# interface.net
KiCad netlist of a schematic drawn in Altium Designer
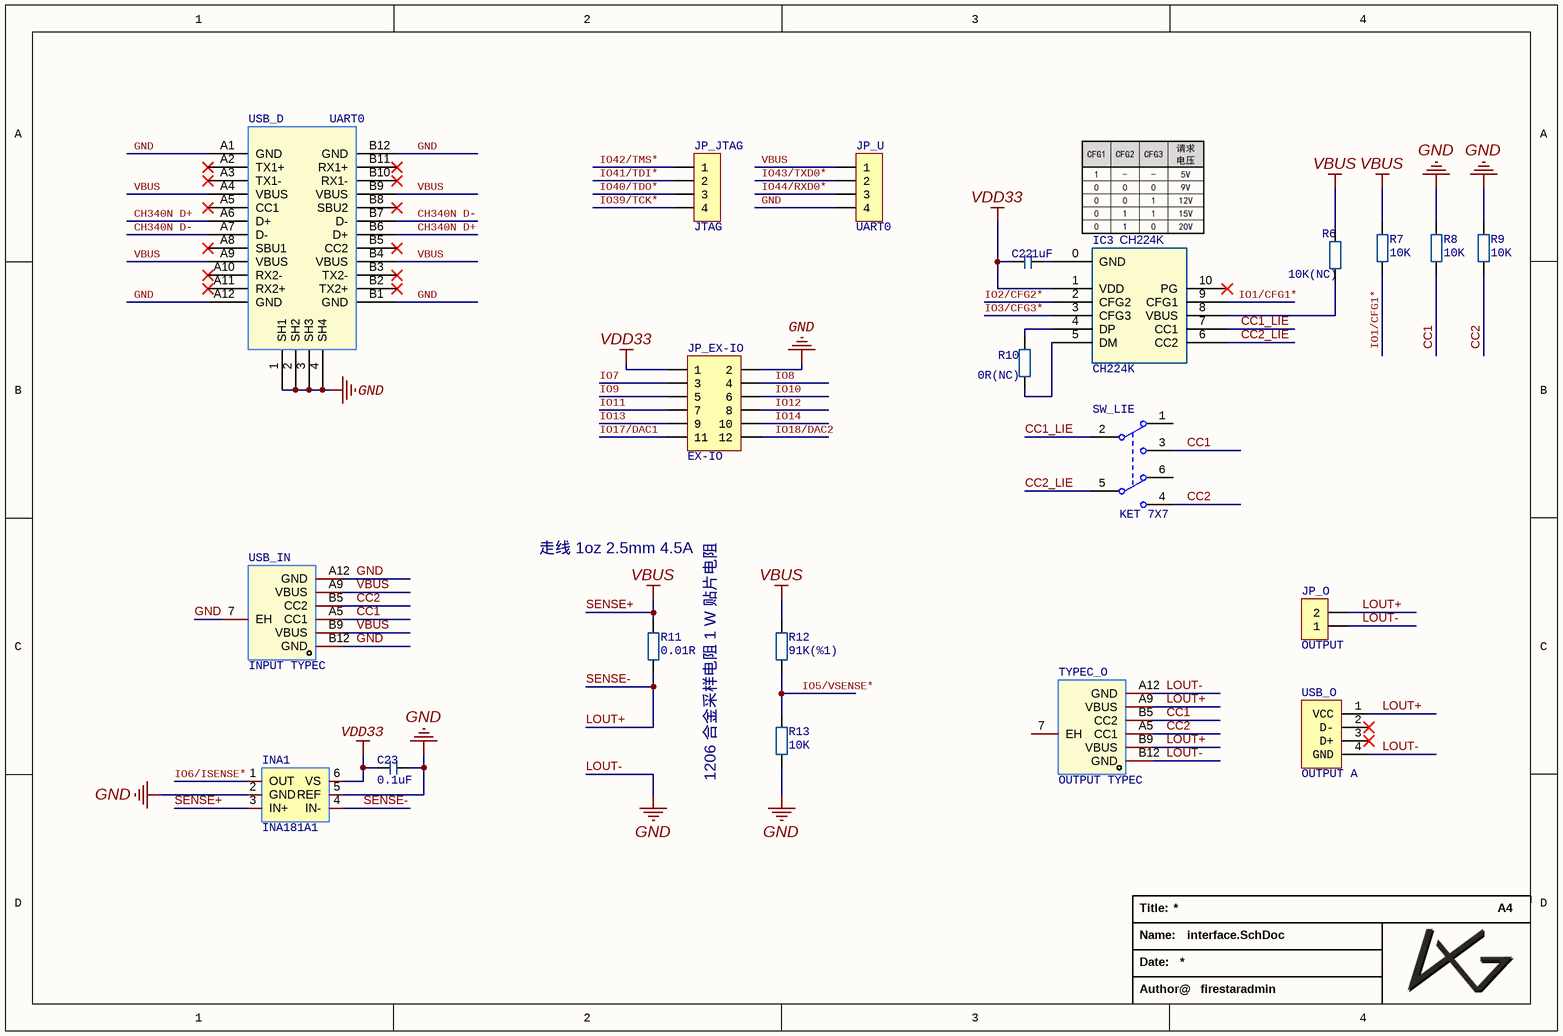
[diagram p0: interface.SchDoc]

(export (version "E")
  (design (tool "Eeschema 10.0.6"))
  (components
    (comp (ref "C22")
      (value "1uF")
      (footprint "C 0603_L")
      (description "无极性贴片电容")
      (fields (field (name "版权归属") "源创客"))
      (libsource (lib "SCH-电阻-电容-电感") (part "C"))
    )
    (comp (ref "C23")
      (value "0.1uF")
      (footprint "C 0603_L")
      (description "无极性贴片电容")
      (fields (field (name "版权归属") "源创客"))
      (libsource (lib "SCH-电阻-电容-电感") (part "C"))
    )
    (comp (ref "IC3")
      (value "CH224K")
      (footprint "ESSOP10-1mm")
      (libsource (lib "SCH-电源类芯片") (part "CH224K"))
    )
    (comp (ref "INA1")
      (value "INA181A1")
      (footprint "SOT23-6L")
      (description "电流检测")
      (libsource (lib "SCH-IC芯片") (part "INA181A1"))
    )
    (comp (ref "JP_EX-IO")
      (value "EX-IO")
      (footprint "HDR2.54-LI-2x6P")
      (description "6*2P接插件")
      (fields (field (name "版权归属") "源创客"))
      (libsource (lib "SCH-接插件-2.54mm") (part "Header  6X2"))
    )
    (comp (ref "JP_JTAG")
      (value "JTAG")
      (footprint "HDR2.54-LI-4P")
      (description "4P接插件")
      (fields (field (name "版权归属") "源创客"))
      (libsource (lib "SCH-接插件-2.54mm") (part "Header 4"))
    )
    (comp (ref "JP_O")
      (value "OUTPUT")
      (footprint "KF301-5.0-2P")
      (description "2P接插件")
      (fields (field (name "版权归属") "源创客"))
      (libsource (lib "SCH-接插件-5.0mm") (part "Header 2"))
    )
    (comp (ref "JP_U")
      (value "UART0")
      (footprint "HDR2.54-LI-4P")
      (description "4P接插件")
      (fields (field (name "版权归属") "源创客"))
      (libsource (lib "SCH-接插件-2.54mm") (part "Header 4"))
    )
    (comp (ref "R6")
      (value "10K(NC)")
      (footprint "R 0603_L")
      (description "贴片电阻")
      (fields (field (name "版权归属") "源创客"))
      (libsource (lib "SCH-电阻-电容-电感") (part "R"))
    )
    (comp (ref "R7")
      (value "10K")
      (footprint "R 0603_L")
      (description "贴片电阻")
      (fields (field (name "版权归属") "源创客"))
      (libsource (lib "SCH-电阻-电容-电感") (part "R"))
    )
    (comp (ref "R8")
      (value "10K")
      (footprint "R 0603_L")
      (description "贴片电阻")
      (fields (field (name "版权归属") "源创客"))
      (libsource (lib "SCH-电阻-电容-电感") (part "R"))
    )
    (comp (ref "R9")
      (value "10K")
      (footprint "R 0603_L")
      (description "贴片电阻")
      (fields (field (name "版权归属") "源创客"))
      (libsource (lib "SCH-电阻-电容-电感") (part "R"))
    )
    (comp (ref "R10")
      (value "0R(NC)")
      (footprint "R 0603_L")
      (description "贴片电阻")
      (fields (field (name "版权归属") "源创客"))
      (libsource (lib "SCH-电阻-电容-电感") (part "R"))
    )
    (comp (ref "R11")
      (value "0.01R")
      (footprint "R 1206_L")
      (description "1206 合金采样电阻 1 W 贴片电阻")
      (fields (field (name "版权归属") "源创客"))
      (libsource (lib "SCH-电阻-电容-电感") (part "R"))
    )
    (comp (ref "R12")
      (value "91K(%1)")
      (footprint "R 0603_L")
      (description "贴片电阻")
      (fields (field (name "版权归属") "源创客"))
      (libsource (lib "SCH-电阻-电容-电感") (part "R"))
    )
    (comp (ref "R13")
      (value "10K")
      (footprint "R 0603_L")
      (description "贴片电阻")
      (fields (field (name "版权归属") "源创客"))
      (libsource (lib "SCH-电阻-电容-电感") (part "R"))
    )
    (comp (ref "SW_LIE")
      (value "KET 7X7")
      (footprint "KFT DIP-7X7")
      (description "7*7自锁开关")
      (fields (field (name "版权归属") "源创客"))
      (libsource (lib "SCH-按键-开关") (part "KET 7X7"))
    )
    (comp (ref "TYPEC_O")
      (value "OUTPUT TYPEC")
      (footprint "TYPE-C-6P")
      (fields (field (name "MANUFACTURER") "SHOU HAN(首韩)") (field (name "MANUFACTURER PART") "TYPE-C 6P"))
      (libsource (lib "SCH-接口类") (part "TYPE-C 6P"))
    )
    (comp (ref "USB_D")
      (value "UART0")
      (footprint "TYPE-C-16P")
      (description "Type-C 16Pin")
      (libsource (lib "SCH-接口类") (part "TypeC-16P"))
    )
    (comp (ref "USB_IN")
      (value "INPUT TYPEC")
      (footprint "TYPE-C-6P")
      (fields (field (name "MANUFACTURER") "SHOU HAN(首韩)") (field (name "MANUFACTURER PART") "TYPE-C 6P"))
      (libsource (lib "SCH-接口类") (part "TYPE-C 6P"))
    )
    (comp (ref "USB_O")
      (value "OUTPUT A")
      (footprint "USB-A/S_B")
      (description "USB-A型母接口")
      (fields (field (name "版权归属") "源创客"))
      (libsource (lib "SCH-接口类") (part "USB-A/S"))
    )
  )
  (nets
    (net (code "1") (name "/CC1") (class "Default")
      (node (ref "R8") (pin "2") (pinfunction "2_2") (pintype "passive"))
      (node (ref "SW_LIE") (pin "3") (pinfunction "NO1_3") (pintype "passive"))
      (node (ref "TYPEC_O") (pin "B5") (pinfunction "CC2_B5") (pintype "passive"))
      (node (ref "USB_IN") (pin "A5") (pinfunction "CC1_A5") (pintype "passive"))
    )
    (net (code "2") (name "/CC1_LIE") (class "Default")
      (node (ref "IC3") (pin "7") (pinfunction "CC1_7") (pintype "passive"))
      (node (ref "SW_LIE") (pin "2") (pinfunction "COM2_2") (pintype "passive"))
    )
    (net (code "3") (name "/CC2") (class "Default")
      (node (ref "R9") (pin "2") (pinfunction "2_2") (pintype "passive"))
      (node (ref "SW_LIE") (pin "4") (pinfunction "NO2_4") (pintype "passive"))
      (node (ref "TYPEC_O") (pin "A5") (pinfunction "CC1_A5") (pintype "passive"))
      (node (ref "USB_IN") (pin "B5") (pinfunction "CC2_B5") (pintype "passive"))
    )
    (net (code "4") (name "/CC2_LIE") (class "Default")
      (node (ref "IC3") (pin "6") (pinfunction "CC2_6") (pintype "passive"))
      (node (ref "SW_LIE") (pin "5") (pinfunction "COM2_5") (pintype "passive"))
    )
    (net (code "5") (name "/CH340N D+") (class "Default")
      (node (ref "USB_D") (pin "A6") (pinfunction "D+_A6") (pintype "passive"))
      (node (ref "USB_D") (pin "B6") (pinfunction "D+_B6") (pintype "passive"))
    )
    (net (code "6") (name "/CH340N D-") (class "Default")
      (node (ref "USB_D") (pin "A7") (pinfunction "D-_A7") (pintype "passive"))
      (node (ref "USB_D") (pin "B7") (pinfunction "D-_B7") (pintype "passive"))
    )
    (net (code "7") (name "/IO1{slash}CFG1*") (class "Default")
      (node (ref "IC3") (pin "9") (pinfunction "CFG1_9") (pintype "passive"))
      (node (ref "R7") (pin "2") (pinfunction "2_2") (pintype "passive"))
    )
    (net (code "8") (name "/IO2{slash}CFG2*") (class "Default")
      (node (ref "IC3") (pin "2") (pinfunction "CFG2_2") (pintype "passive"))
    )
    (net (code "9") (name "/IO3{slash}CFG3*") (class "Default")
      (node (ref "IC3") (pin "3") (pinfunction "CFG3_3") (pintype "passive"))
    )
    (net (code "10") (name "/IO5{slash}VSENSE*") (class "Default")
      (node (ref "R12") (pin "1") (pinfunction "1_1") (pintype "passive"))
      (node (ref "R13") (pin "2") (pinfunction "2_2") (pintype "passive"))
    )
    (net (code "11") (name "/IO6{slash}ISENSE*") (class "Default")
      (node (ref "INA1") (pin "1") (pinfunction "OUT_1") (pintype "passive"))
    )
    (net (code "12") (name "/IO7") (class "Default")
      (node (ref "JP_EX-IO") (pin "3") (pinfunction "3_3") (pintype "passive"))
    )
    (net (code "13") (name "/IO8") (class "Default")
      (node (ref "JP_EX-IO") (pin "4") (pinfunction "4_4") (pintype "passive"))
    )
    (net (code "14") (name "/IO9") (class "Default")
      (node (ref "JP_EX-IO") (pin "5") (pinfunction "5_5") (pintype "passive"))
    )
    (net (code "15") (name "/IO10") (class "Default")
      (node (ref "JP_EX-IO") (pin "6") (pinfunction "6_6") (pintype "passive"))
    )
    (net (code "16") (name "/IO11") (class "Default")
      (node (ref "JP_EX-IO") (pin "7") (pinfunction "7_7") (pintype "passive"))
    )
    (net (code "17") (name "/IO12") (class "Default")
      (node (ref "JP_EX-IO") (pin "8") (pinfunction "8_8") (pintype "passive"))
    )
    (net (code "18") (name "/IO13") (class "Default")
      (node (ref "JP_EX-IO") (pin "9") (pinfunction "9_9") (pintype "passive"))
    )
    (net (code "19") (name "/IO14") (class "Default")
      (node (ref "JP_EX-IO") (pin "10") (pinfunction "10_10") (pintype "passive"))
    )
    (net (code "20") (name "/IO17{slash}DAC1") (class "Default")
      (node (ref "JP_EX-IO") (pin "11") (pinfunction "11_11") (pintype "passive"))
    )
    (net (code "21") (name "/IO18{slash}DAC2") (class "Default")
      (node (ref "JP_EX-IO") (pin "12") (pinfunction "12_12") (pintype "passive"))
    )
    (net (code "22") (name "/IO39{slash}TCK*") (class "Default")
      (node (ref "JP_JTAG") (pin "4") (pinfunction "4_4") (pintype "passive"))
    )
    (net (code "23") (name "/IO40{slash}TDO*") (class "Default")
      (node (ref "JP_JTAG") (pin "3") (pinfunction "3_3") (pintype "passive"))
    )
    (net (code "24") (name "/IO41{slash}TDI*") (class "Default")
      (node (ref "JP_JTAG") (pin "2") (pinfunction "2_2") (pintype "passive"))
    )
    (net (code "25") (name "/IO42{slash}TMS*") (class "Default")
      (node (ref "JP_JTAG") (pin "1") (pinfunction "1_1") (pintype "passive"))
    )
    (net (code "26") (name "/IO43{slash}TXD0*") (class "Default")
      (node (ref "JP_U") (pin "2") (pinfunction "2_2") (pintype "passive"))
    )
    (net (code "27") (name "/IO44{slash}RXD0*") (class "Default")
      (node (ref "JP_U") (pin "3") (pinfunction "3_3") (pintype "passive"))
    )
    (net (code "28") (name "/LOUT+") (class "Default")
      (node (ref "INA1") (pin "4") (pinfunction "IN-_4") (pintype "passive"))
      (node (ref "JP_O") (pin "2") (pinfunction "2_2") (pintype "passive"))
      (node (ref "R11") (pin "1") (pinfunction "1_1") (pintype "passive"))
      (node (ref "TYPEC_O") (pin "A9") (pinfunction "VBUS_A9") (pintype "passive"))
      (node (ref "TYPEC_O") (pin "B9") (pinfunction "VBUS_B9") (pintype "passive"))
      (node (ref "USB_O") (pin "1") (pinfunction "VCC_1") (pintype "passive"))
    )
    (net (code "29") (name "GND") (class "Default")
      (node (ref "C23") (pin "1") (pinfunction "1_1") (pintype "passive"))
      (node (ref "INA1") (pin "2") (pinfunction "GND_2") (pintype "passive"))
      (node (ref "INA1") (pin "5") (pinfunction "REF_5") (pintype "passive"))
      (node (ref "JP_EX-IO") (pin "2") (pinfunction "2_2") (pintype "passive"))
      (node (ref "JP_O") (pin "1") (pinfunction "1_1") (pintype "passive"))
      (node (ref "JP_U") (pin "4") (pinfunction "4_4") (pintype "passive"))
      (node (ref "R13") (pin "1") (pinfunction "1_1") (pintype "passive"))
      (node (ref "R8") (pin "1") (pinfunction "1_1") (pintype "passive"))
      (node (ref "R9") (pin "1") (pinfunction "1_1") (pintype "passive"))
      (node (ref "TYPEC_O") (pin "A12") (pinfunction "GND_A12") (pintype "passive"))
      (node (ref "TYPEC_O") (pin "B12") (pinfunction "GND_B12") (pintype "passive"))
      (node (ref "USB_D") (pin "1") (pinfunction "SH1_1") (pintype "passive"))
      (node (ref "USB_D") (pin "2") (pinfunction "SH2_2") (pintype "passive"))
      (node (ref "USB_D") (pin "3") (pinfunction "SH3_3") (pintype "passive"))
      (node (ref "USB_D") (pin "4") (pinfunction "SH4_4") (pintype "passive"))
      (node (ref "USB_D") (pin "A1") (pinfunction "GND_A1") (pintype "passive"))
      (node (ref "USB_D") (pin "A12") (pinfunction "GND_A12") (pintype "passive"))
      (node (ref "USB_D") (pin "B1") (pinfunction "GND_B1") (pintype "passive"))
      (node (ref "USB_D") (pin "B12") (pinfunction "GND_B12") (pintype "passive"))
      (node (ref "USB_IN") (pin "7") (pinfunction "EH_7") (pintype "passive"))
      (node (ref "USB_IN") (pin "A12") (pinfunction "GND_A12") (pintype "passive"))
      (node (ref "USB_IN") (pin "B12") (pinfunction "GND_B12") (pintype "passive"))
      (node (ref "USB_O") (pin "4") (pinfunction "GND_4") (pintype "passive"))
    )
    (net (code "30") (name "Net-(IC3-DM)") (class "Default")
      (node (ref "IC3") (pin "5") (pinfunction "DM_5") (pintype "passive"))
      (node (ref "R10") (pin "2") (pinfunction "2_2") (pintype "passive"))
    )
    (net (code "31") (name "Net-(IC3-DP)") (class "Default")
      (node (ref "IC3") (pin "4") (pinfunction "DP_4") (pintype "passive"))
      (node (ref "R10") (pin "1") (pinfunction "1_1") (pintype "passive"))
    )
    (net (code "32") (name "Net-(IC3-GND)") (class "Default")
      (node (ref "C22") (pin "1") (pinfunction "1_1") (pintype "passive"))
      (node (ref "IC3") (pin "0") (pinfunction "GND_0") (pintype "passive"))
    )
    (net (code "33") (name "Net-(IC3-VBUS)") (class "Default")
      (node (ref "IC3") (pin "8") (pinfunction "VBUS_8") (pintype "passive"))
      (node (ref "R6") (pin "2") (pinfunction "2_2") (pintype "passive"))
    )
    (net (code "34") (name "VBUS") (class "Default")
      (node (ref "INA1") (pin "3") (pinfunction "IN+_3") (pintype "passive"))
      (node (ref "JP_U") (pin "1") (pinfunction "1_1") (pintype "passive"))
      (node (ref "R11") (pin "2") (pinfunction "2_2") (pintype "passive"))
      (node (ref "R12") (pin "2") (pinfunction "2_2") (pintype "passive"))
      (node (ref "R6") (pin "1") (pinfunction "1_1") (pintype "passive"))
      (node (ref "R7") (pin "1") (pinfunction "1_1") (pintype "passive"))
      (node (ref "USB_D") (pin "A4") (pinfunction "VBUS_A4") (pintype "passive"))
      (node (ref "USB_D") (pin "A9") (pinfunction "VBUS_A9") (pintype "passive"))
      (node (ref "USB_D") (pin "B4") (pinfunction "VBUS_B4") (pintype "passive"))
      (node (ref "USB_D") (pin "B9") (pinfunction "VBUS_B9") (pintype "passive"))
      (node (ref "USB_IN") (pin "A9") (pinfunction "VBUS_A9") (pintype "passive"))
      (node (ref "USB_IN") (pin "B9") (pinfunction "VBUS_B9") (pintype "passive"))
    )
    (net (code "35") (name "VDD33") (class "Default")
      (node (ref "C22") (pin "2") (pinfunction "2_2") (pintype "passive"))
      (node (ref "C23") (pin "2") (pinfunction "2_2") (pintype "passive"))
      (node (ref "IC3") (pin "1") (pinfunction "VDD_1") (pintype "passive"))
      (node (ref "INA1") (pin "6") (pinfunction "VS_6") (pintype "passive"))
      (node (ref "JP_EX-IO") (pin "1") (pinfunction "1_1") (pintype "passive"))
    )
    (net (code "36") (name "unconnected-(IC3-PG-Pad10)") (class "Default")
      (node (ref "IC3") (pin "10") (pinfunction "PG_10") (pintype "passive+no_connect"))
    )
    (net (code "37") (name "unconnected-(SW_LIE-NC1-Pad1)") (class "Default")
      (node (ref "SW_LIE") (pin "1") (pinfunction "NC1_1") (pintype "passive"))
    )
    (net (code "38") (name "unconnected-(SW_LIE-NC2-Pad6)") (class "Default")
      (node (ref "SW_LIE") (pin "6") (pinfunction "NC2_6") (pintype "passive"))
    )
    (net (code "39") (name "unconnected-(TYPEC_O-EH-Pad7)") (class "Default")
      (node (ref "TYPEC_O") (pin "7") (pinfunction "EH_7") (pintype "passive"))
    )
    (net (code "40") (name "unconnected-(USB_D-CC1-PadA5)") (class "Default")
      (node (ref "USB_D") (pin "A5") (pinfunction "CC1_A5") (pintype "passive+no_connect"))
    )
    (net (code "41") (name "unconnected-(USB_D-CC2-PadB5)") (class "Default")
      (node (ref "USB_D") (pin "B5") (pinfunction "CC2_B5") (pintype "passive+no_connect"))
    )
    (net (code "42") (name "unconnected-(USB_D-RX1+-PadB11)") (class "Default")
      (node (ref "USB_D") (pin "B11") (pinfunction "RX1+_B11") (pintype "passive+no_connect"))
    )
    (net (code "43") (name "unconnected-(USB_D-RX1--PadB10)") (class "Default")
      (node (ref "USB_D") (pin "B10") (pinfunction "RX1-_B10") (pintype "passive+no_connect"))
    )
    (net (code "44") (name "unconnected-(USB_D-RX2+-PadA11)") (class "Default")
      (node (ref "USB_D") (pin "A11") (pinfunction "RX2+_A11") (pintype "passive+no_connect"))
    )
    (net (code "45") (name "unconnected-(USB_D-RX2--PadA10)") (class "Default")
      (node (ref "USB_D") (pin "A10") (pinfunction "RX2-_A10") (pintype "passive+no_connect"))
    )
    (net (code "46") (name "unconnected-(USB_D-SBU1-PadA8)") (class "Default")
      (node (ref "USB_D") (pin "A8") (pinfunction "SBU1_A8") (pintype "passive+no_connect"))
    )
    (net (code "47") (name "unconnected-(USB_D-SBU2-PadB8)") (class "Default")
      (node (ref "USB_D") (pin "B8") (pinfunction "SBU2_B8") (pintype "passive+no_connect"))
    )
    (net (code "48") (name "unconnected-(USB_D-TX1+-PadA2)") (class "Default")
      (node (ref "USB_D") (pin "A2") (pinfunction "TX1+_A2") (pintype "passive+no_connect"))
    )
    (net (code "49") (name "unconnected-(USB_D-TX1--PadA3)") (class "Default")
      (node (ref "USB_D") (pin "A3") (pinfunction "TX1-_A3") (pintype "passive+no_connect"))
    )
    (net (code "50") (name "unconnected-(USB_D-TX2+-PadB2)") (class "Default")
      (node (ref "USB_D") (pin "B2") (pinfunction "TX2+_B2") (pintype "passive+no_connect"))
    )
    (net (code "51") (name "unconnected-(USB_D-TX2--PadB3)") (class "Default")
      (node (ref "USB_D") (pin "B3") (pinfunction "TX2-_B3") (pintype "passive+no_connect"))
    )
    (net (code "52") (name "unconnected-(USB_O-D+-Pad3)") (class "Default")
      (node (ref "USB_O") (pin "3") (pinfunction "D+_3") (pintype "passive+no_connect"))
    )
    (net (code "53") (name "unconnected-(USB_O-D--Pad2)") (class "Default")
      (node (ref "USB_O") (pin "2") (pinfunction "D-_2") (pintype "passive+no_connect"))
    )
  )
)
